# POWER.net
KiCad netlist of a schematic drawn in Altium Designer
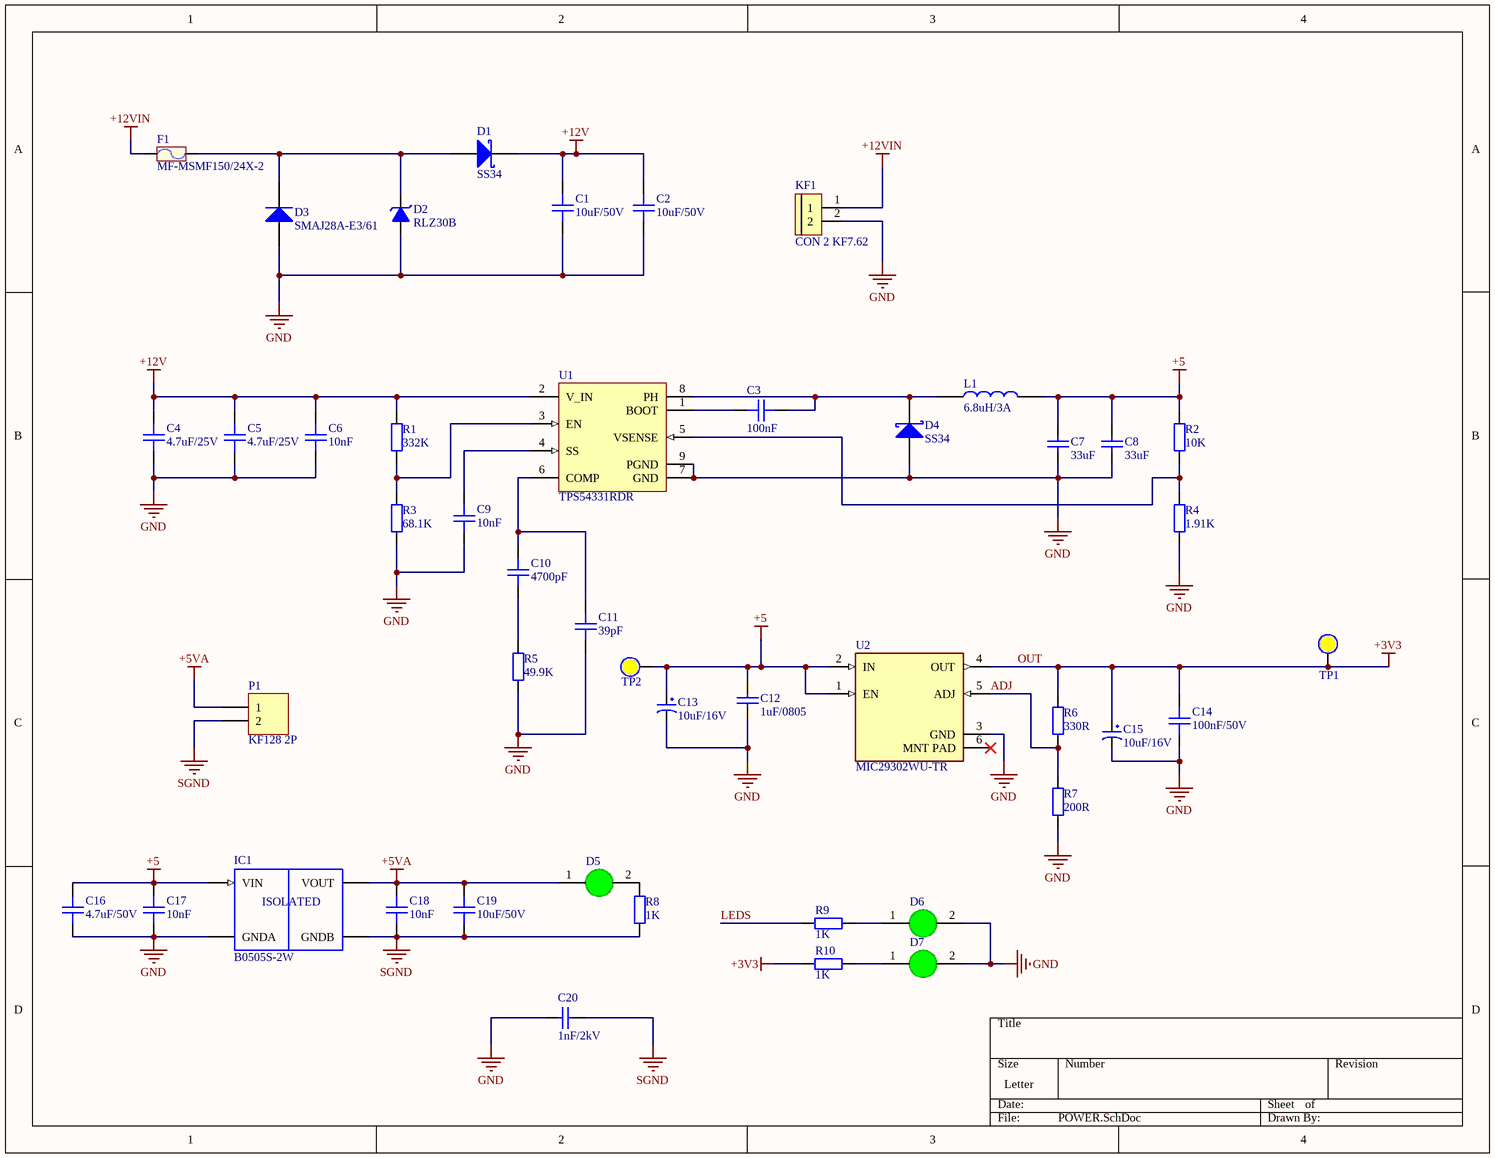
[diagram p0: POWER.SchDoc]

(export (version "E")
  (design (tool "Eeschema 10.0.6"))
  (components
    (comp (ref "C1")
      (value "10uF/50V")
      (footprint "1210")
      (description "CAP CER 10uF/50V 1210")
      (fields (field (name "MANUFACTURER") "Yageo") (field (name "PART NUMBER") "C1210"))
      (libsource (lib "Integrated_Library_gateway_tbl") (part "CAP_CER_1210_10uF"))
    )
    (comp (ref "C2")
      (value "10uF/50V")
      (footprint "1210")
      (description "CAP CER 10uF/50V 1210")
      (fields (field (name "MANUFACTURER") "Yageo") (field (name "PART NUMBER") "C1210"))
      (libsource (lib "Integrated_Library_gateway_tbl") (part "CAP_CER_1210_10uF"))
    )
    (comp (ref "C3")
      (value "100nF")
      (footprint "CAPC-0603 (1608)")
      (description "CAP CER 0.22UF 50V Y5V 0603")
      (fields (field (name "MPN") "CC0603ZRY5V9BB224"))
      (libsource (lib "Integrated_Library_gateway_tbl") (part "CC0603ZRY5V9BB224"))
    )
    (comp (ref "C4")
      (value "4.7uF/25V")
      (footprint "CAPC-1210 (3225)")
      (description "CAP CER 1UF 50V X7R 1210")
      (fields (field (name "MPN") "CC1210KKX7R9BB105") (field (name "MFR") "Yageo"))
      (libsource (lib "Integrated_Library_gateway_tbl") (part "CC1210KKX7R9BB105"))
    )
    (comp (ref "C5")
      (value "4.7uF/25V")
      (footprint "CAPC-1210 (3225)")
      (description "CAP CER 1UF 50V X7R 1210")
      (fields (field (name "MPN") "CC1210KKX7R9BB105") (field (name "MFR") "Yageo"))
      (libsource (lib "Integrated_Library_gateway_tbl") (part "CC1210KKX7R9BB105"))
    )
    (comp (ref "C6")
      (value "10nF")
      (footprint "CAPC-0603 (1608)")
      (description "CAP CER 10nF 16V 10% X7R 0603")
      (fields (field (name "MPN") "CC0603KRX7R7BB103"))
      (libsource (lib "Integrated_Library_gateway_tbl") (part "CC0603KRX7R7BB103"))
    )
    (comp (ref "C7")
      (value "33uF")
      (footprint "tu 1206")
      (description "Dán")
      (libsource (lib "Integrated_Library_gateway_tbl") (part "Tu 1206 100pF 50V 5%"))
    )
    (comp (ref "C8")
      (value "33uF")
      (footprint "tu 1206")
      (description "Dán")
      (libsource (lib "Integrated_Library_gateway_tbl") (part "Tu 1206 100pF 50V 5%"))
    )
    (comp (ref "C9")
      (value "10nF")
      (footprint "CAPC-0603 (1608)")
      (description "CAP CER 10nF 16V 10% X7R 0603")
      (fields (field (name "MPN") "CC0603KRX7R7BB103"))
      (libsource (lib "Integrated_Library_gateway_tbl") (part "CC0603KRX7R7BB103"))
    )
    (comp (ref "C10")
      (value "4700pF")
      (footprint "CAPC-0603 (1608)")
      (description "CAP CER 8200PF 50V X7R 0603")
      (fields (field (name "MPN") "CC0603KRX7R9BB822") (field (name "MFR") "Yageo"))
      (libsource (lib "Integrated_Library_gateway_tbl") (part "CC0603KRX7R9BB822"))
    )
    (comp (ref "C11")
      (value "39pF")
      (footprint "CAPC-0603 (1608)")
      (description "CAP CER 56PF 50V 5% COG/NPO 0603")
      (fields (field (name "MPN") "CC0603JRNPO9BN560"))
      (libsource (lib "Integrated_Library_gateway_tbl") (part "CC0603JRNPO9BN560"))
    )
    (comp (ref "C12")
      (value "1uF/0805")
      (footprint "tu 0805")
      (description "Dán")
      (libsource (lib "Integrated_Library_gateway_tbl") (part "Tu 0805 104 50V 10%"))
    )
    (comp (ref "C13")
      (value "10uF/16V")
      (footprint "2312")
      (description "CAP TANT 100uF/10V 2312")
      (fields (field (name "MANUFACTURER") "AVX") (field (name "PART NUMBER") "TAJC107K010RNJ"))
      (libsource (lib "Integrated_Library_gateway_tbl") (part "CAP_TANT_2312_100uF"))
    )
    (comp (ref "C14")
      (value "100nF/50V")
      (footprint "C0805")
      (description "CAP CER 100nF/50V 0805")
      (fields (field (name "MANUFACTURER") "Samsung") (field (name "PART NUMBER") "C0805"))
      (libsource (lib "Integrated_Library_gateway_tbl") (part "CAP_CER_0805_100nF"))
    )
    (comp (ref "C15")
      (value "10uF/16V")
      (footprint "2312")
      (description "CAP TANT 100uF/10V 2312")
      (fields (field (name "MANUFACTURER") "AVX") (field (name "PART NUMBER") "TAJC107K010RNJ"))
      (libsource (lib "Integrated_Library_gateway_tbl") (part "CAP_TANT_2312_100uF"))
    )
    (comp (ref "C16")
      (value "4.7uF/50V")
      (footprint "CAPC-0805 (2012)")
      (description "CAP CER 4.7uF -20% +80% 10V Y5V 0805")
      (fields (field (name "MPN") "CC0805ZRY5V6BB475"))
      (libsource (lib "Integrated_Library_gateway_tbl") (part "CC0805ZRY5V6BB475"))
    )
    (comp (ref "C17")
      (value "10nF")
      (footprint "CAPC-0603 (1608)")
      (description "CAP CER 10nF 16V 10% X7R 0603")
      (fields (field (name "MPN") "CC0603KRX7R7BB103"))
      (libsource (lib "Integrated_Library_gateway_tbl") (part "CC0603KRX7R7BB103"))
    )
    (comp (ref "C18")
      (value "10nF")
      (footprint "CAPC-0603 (1608)")
      (description "CAP CER 10nF 16V 10% X7R 0603")
      (fields (field (name "MPN") "CC0603KRX7R7BB103"))
      (libsource (lib "Integrated_Library_gateway_tbl") (part "CC0603KRX7R7BB103"))
    )
    (comp (ref "C19")
      (value "10uF/50V")
      (footprint "CAPC-0805 (2012)")
      (description "CAP CER 22uF 20% 10V X5R 0805")
      (fields (field (name "MPN") "CC0805MKX5R6BB226"))
      (libsource (lib "Integrated_Library_gateway_tbl") (part "CC0805MKX5R6BB226"))
    )
    (comp (ref "C20")
      (value "1nF/2kV")
      (footprint "tu 1206")
      (description "Dán")
      (libsource (lib "Integrated_Library_gateway_tbl") (part "Tu 1206 470pF 50V 10%"))
    )
    (comp (ref "D1")
      (value "SS34")
      (footprint "DIODE_DO214AC_SMA")
      (description "DIODE SCHOTTKY 40V 3A SMA")
      (libsource (lib "Integrated_Library_gateway_tbl") (part "SS34"))
    )
    (comp (ref "D2")
      (value "RLZ30B")
      (footprint "SOD_80")
      (description "ZMM15 15V 500mW SMD SOD-80")
      (fields (field (name "MANUFACTURER") "On Semiconductor") (field (name "PART NUMBER") "ZMM15"))
      (libsource (lib "Integrated_Library_gateway_tbl") (part "DIO_ZMM15"))
    )
    (comp (ref "D3")
      (value "SMAJ28A-E3/61")
      (footprint "VISH-DO-214AC-2_L")
      (fields (field (name "MANUFACTURER") "Vishay Semiconductor"))
      (libsource (lib "Integrated_Library_gateway_tbl") (part "VISH-K1A2-2"))
    )
    (comp (ref "D4")
      (value "SS34")
      (footprint "DIODE_DO214AC_SMA")
      (description "DIODE SCHOTTKY 40V 3A SMA")
      (libsource (lib "Integrated_Library_gateway_tbl") (part "SS34"))
    )
    (comp (ref "D5")
      (value "~")
      (footprint "LED_0805_GREEN")
      (description "LED GREEN CLEAR 2V4 20mA 0805 SMD")
      (fields (field (name "MPN") "17-21/G6C-FM1N2B/3T"))
      (libsource (lib "Integrated_Library_gateway_tbl") (part "17-21/G6C-FM1N2B/3T"))
    )
    (comp (ref "D6")
      (value "~")
      (footprint "LED_0805_GREEN")
      (description "LED GREEN CLEAR 2V4 20mA 0805 SMD")
      (fields (field (name "MPN") "17-21/G6C-FM1N2B/3T"))
      (libsource (lib "Integrated_Library_gateway_tbl") (part "17-21/G6C-FM1N2B/3T"))
    )
    (comp (ref "D7")
      (value "~")
      (footprint "LED_0805_GREEN")
      (description "LED GREEN CLEAR 2V4 20mA 0805 SMD")
      (fields (field (name "MPN") "17-21/G6C-FM1N2B/3T"))
      (libsource (lib "Integrated_Library_gateway_tbl") (part "17-21/G6C-FM1N2B/3T"))
    )
    (comp (ref "F1")
      (value "MF-MSMF150/24X-2")
      (footprint "1812")
      (description "MF-MSMF250/16 16V 2.5A1812")
      (fields (field (name "MANUFACTURER") "Bourns") (field (name "PART NUMBER") "1812"))
      (libsource (lib "Integrated_Library_gateway_tbl") (part "FUSE_16V_2.5A"))
    )
    (comp (ref "IC1")
      (value "B0505S-2W")
      (footprint "B0505S-2W")
      (fields (field (name "MF") "MORNSUN"))
      (libsource (lib "Integrated_Library_gateway_tbl") (part "B0505S-2W"))
    )
    (comp (ref "KF1")
      (value "CON 2 KF7.62")
      (footprint "CON 2 KF7.62")
      (description "Cắm")
      (libsource (lib "Altium_Lib_by_KhueNguyenCreator") (part "CON 2 KF7.62"))
    )
    (comp (ref "L1")
      (value "6.8uH/3A")
      (footprint "Cuon Cam 12x12x10")
      (description "Dán")
      (libsource (lib "Integrated_Library_gateway_tbl") (part "CUON CAM 100uH SMD"))
    )
    (comp (ref "P1")
      (value "KF128 2P")
      (footprint "KF128_2P")
      (description "Header, 2-Pin, pitch 5.08mm")
      (fields (field (name "MPN") "KF128-2P"))
      (libsource (lib "Integrated_Library_gateway_tbl") (part "KF128 2P"))
    )
    (comp (ref "R1")
      (value "332K")
      (footprint "RESC-0603 (1608)")
      (description "RES SMD 330K OHM 1% 1/10W 0603")
      (fields (field (name "MPN") "RC0603FR-07330KL"))
      (libsource (lib "Integrated_Library_gateway_tbl") (part "RC0603FR-07330KL"))
    )
    (comp (ref "R2")
      (value "10K")
      (footprint "RESC-0805 (2012)")
      (description "RES SMD 10K OHM 1% 1/8W 0805")
      (fields (field (name "MPN") "RC0805FR-0710KL"))
      (libsource (lib "Integrated_Library_gateway_tbl") (part "RC0805FR-0710KL"))
    )
    (comp (ref "R3")
      (value "68.1K")
      (footprint "RESC-0603 (1608)")
      (description "RES SMD 68K OHM 1% 1/10W 0603")
      (fields (field (name "MPN") "RC0603FR-0768KL"))
      (libsource (lib "Integrated_Library_gateway_tbl") (part "RC0603FR-0768KL"))
    )
    (comp (ref "R4")
      (value "1.91K")
      (footprint "RESC-0805 (2012)")
      (description "RES SMD 1.1K OHM 1% 1/8W 0805")
      (fields (field (name "MPN") "RC0805FR-071K1L"))
      (libsource (lib "Integrated_Library_gateway_tbl") (part "RC0805FR-071K1L"))
    )
    (comp (ref "R5")
      (value "49.9K")
      (footprint "RESC-0603 (1608)")
      (description "RES SMD 47K OHM 1% 1/10W 0603")
      (fields (field (name "MPN") "RC0603FR0747KL"))
      (libsource (lib "Integrated_Library_gateway_tbl") (part "RC0603FR0747KL"))
    )
    (comp (ref "R6")
      (value "330R")
      (footprint "RESC-0805 (2012)")
      (description "RES SMD 330 OHM 1% 1/8W 0805")
      (fields (field (name "MPN") "RC0805FR-07330RL"))
      (libsource (lib "Integrated_Library_gateway_tbl") (part "RC0805FR-07330RL"))
    )
    (comp (ref "R7")
      (value "200R")
      (footprint "RESC-0805 (2012)")
      (description "RES SMD 300 OHM 1% 1/8W 0805")
      (fields (field (name "MPN") "RC0805FR-07300RL"))
      (libsource (lib "Integrated_Library_gateway_tbl") (part "RC0805FR-07300RL"))
    )
    (comp (ref "R8")
      (value "1K")
      (footprint "RESC-0805 (2012)")
      (description "RES SMD 1K OHM 1% 1/8W 0805")
      (fields (field (name "MPN") "RC0805FR-071KL"))
      (libsource (lib "Integrated_Library_gateway_tbl") (part "RC0805FR-071KL"))
    )
    (comp (ref "R9")
      (value "1K")
      (footprint "RESC-0805 (2012)")
      (description "RES SMD 1K OHM 1% 1/8W 0805")
      (fields (field (name "MPN") "RC0805FR-071KL"))
      (libsource (lib "") (part "RC0805FR-071KL_1"))
    )
    (comp (ref "R10")
      (value "1K")
      (footprint "RESC-0805 (2012)")
      (description "RES SMD 1K OHM 1% 1/8W 0805")
      (fields (field (name "MPN") "RC0805FR-071KL"))
      (libsource (lib "") (part "RC0805FR-071KL_1"))
    )
    (comp (ref "TP1")
      (value "~")
      (footprint "Test Point 1 MM")
      (description "Test Point")
      (libsource (lib "Integrated_Library_gateway_tbl") (part "Test Point"))
    )
    (comp (ref "TP2")
      (value "~")
      (footprint "Test Point 1 MM")
      (description "Test Point")
      (libsource (lib "") (part "Test Point_1"))
    )
    (comp (ref "U1")
      (value "TPS54331RDR")
      (footprint "SOIC-8-TP")
      (description "Step Down DC-DC Converter")
      (fields (field (name "MPN") "TPS54360DDAR"))
      (libsource (lib "Integrated_Library_gateway_tbl") (part "TPS54360DDAR"))
    )
    (comp (ref "U2")
      (value "MIC29302WU-TR")
      (footprint "FP-C04-012-MFG")
      (description "IC REG LINEAR POS ADJ 3A TO263-5")
      (fields
        (field (name "MANUFACTURER") "Microchip")
        (field (name "OCTOPART") "https://octopart.com/mic29302wu-tr-microchip-66801318")
      )
      (libsource (lib "Integrated_Library_gateway_tbl") (part "0db40f55fda0e91d0d14528974a446d"))
    )
  )
  (nets
    (net (code "1") (name "+3V3") (class "Default")
      (node (ref "C14") (pin "2") (pinfunction "2_2") (pintype "passive"))
      (node (ref "C15") (pin "1") (pinfunction "1_1") (pintype "passive"))
      (node (ref "R10") (pin "1") (pinfunction "1_1") (pintype "passive"))
      (node (ref "R6") (pin "2") (pinfunction "2_2") (pintype "passive"))
      (node (ref "TP1") (pin "0") (pinfunction "0_0") (pintype "passive"))
      (node (ref "U2") (pin "4") (pinfunction "OUT_4") (pintype "output"))
    )
    (net (code "2") (name "+5") (class "Default")
      (node (ref "C12") (pin "1") (pinfunction "1_1") (pintype "passive"))
      (node (ref "C13") (pin "1") (pinfunction "1_1") (pintype "passive"))
      (node (ref "C16") (pin "2") (pinfunction "2_2") (pintype "passive"))
      (node (ref "C17") (pin "2") (pinfunction "2_2") (pintype "passive"))
      (node (ref "C7") (pin "1") (pinfunction "1_1") (pintype "passive"))
      (node (ref "C8") (pin "1") (pinfunction "1_1") (pintype "passive"))
      (node (ref "IC1") (pin "VIN") (pinfunction "VIN_VIN") (pintype "input"))
      (node (ref "L1") (pin "2") (pinfunction "2_2") (pintype "passive"))
      (node (ref "R2") (pin "2") (pinfunction "2_2") (pintype "passive"))
      (node (ref "TP2") (pin "0") (pinfunction "0_0") (pintype "passive"))
      (node (ref "U2") (pin "1") (pinfunction "EN_1") (pintype "input"))
      (node (ref "U2") (pin "2") (pinfunction "IN_2") (pintype "input"))
    )
    (net (code "3") (name "+5VA") (class "Default")
      (node (ref "C18") (pin "2") (pinfunction "2_2") (pintype "passive"))
      (node (ref "C19") (pin "2") (pinfunction "2_2") (pintype "passive"))
      (node (ref "D5") (pin "1") (pinfunction "A_1") (pintype "passive"))
      (node (ref "IC1") (pin "VOUT") (pinfunction "VOUT_VOUT") (pintype "power_in"))
      (node (ref "P1") (pin "1") (pinfunction "1_1") (pintype "passive"))
    )
    (net (code "4") (name "+12V") (class "Default")
      (node (ref "C1") (pin "2") (pinfunction "2_2") (pintype "passive"))
      (node (ref "C2") (pin "2") (pinfunction "2_2") (pintype "passive"))
      (node (ref "C4") (pin "2") (pinfunction "2_2") (pintype "passive"))
      (node (ref "C5") (pin "2") (pinfunction "2_2") (pintype "passive"))
      (node (ref "C6") (pin "2") (pinfunction "2_2") (pintype "passive"))
      (node (ref "D1") (pin "2") (pinfunction "K_2") (pintype "passive"))
      (node (ref "R1") (pin "2") (pinfunction "2_2") (pintype "passive"))
      (node (ref "U1") (pin "2") (pinfunction "V_IN_2") (pintype "passive"))
    )
    (net (code "5") (name "+12VIN") (class "Default")
      (node (ref "F1") (pin "1") (pinfunction "1_1") (pintype "passive"))
      (node (ref "KF1") (pin "1") (pinfunction "1_1") (pintype "passive"))
    )
    (net (code "6") (name "/ADJ") (class "Default")
      (node (ref "R6") (pin "1") (pinfunction "1_1") (pintype "passive"))
      (node (ref "R7") (pin "2") (pinfunction "2_2") (pintype "passive"))
      (node (ref "U2") (pin "5") (pinfunction "ADJ_5") (pintype "input"))
    )
    (net (code "7") (name "/LEDS") (class "Default")
      (node (ref "R9") (pin "1") (pinfunction "1_1") (pintype "passive"))
    )
    (net (code "8") (name "GND") (class "Default")
      (node (ref "C1") (pin "1") (pinfunction "1_1") (pintype "passive"))
      (node (ref "C11") (pin "1") (pinfunction "1_1") (pintype "passive"))
      (node (ref "C12") (pin "2") (pinfunction "2_2") (pintype "passive"))
      (node (ref "C13") (pin "2") (pinfunction "2_2") (pintype "passive"))
      (node (ref "C14") (pin "1") (pinfunction "1_1") (pintype "passive"))
      (node (ref "C15") (pin "2") (pinfunction "2_2") (pintype "passive"))
      (node (ref "C16") (pin "1") (pinfunction "1_1") (pintype "passive"))
      (node (ref "C17") (pin "1") (pinfunction "1_1") (pintype "passive"))
      (node (ref "C2") (pin "1") (pinfunction "1_1") (pintype "passive"))
      (node (ref "C20") (pin "2") (pinfunction "2_2") (pintype "passive"))
      (node (ref "C4") (pin "1") (pinfunction "1_1") (pintype "passive"))
      (node (ref "C5") (pin "1") (pinfunction "1_1") (pintype "passive"))
      (node (ref "C6") (pin "1") (pinfunction "1_1") (pintype "passive"))
      (node (ref "C7") (pin "2") (pinfunction "2_2") (pintype "passive"))
      (node (ref "C8") (pin "2") (pinfunction "2_2") (pintype "passive"))
      (node (ref "C9") (pin "1") (pinfunction "1_1") (pintype "passive"))
      (node (ref "D2") (pin "1") (pinfunction "A_1") (pintype "passive"))
      (node (ref "D3") (pin "2") (pinfunction "A_2") (pintype "passive"))
      (node (ref "D4") (pin "1") (pinfunction "A_1") (pintype "passive"))
      (node (ref "D6") (pin "2") (pinfunction "K_2") (pintype "passive"))
      (node (ref "D7") (pin "2") (pinfunction "K_2") (pintype "passive"))
      (node (ref "IC1") (pin "GNDA") (pinfunction "GNDA_GNDA") (pintype "power_in"))
      (node (ref "KF1") (pin "2") (pinfunction "2_2") (pintype "passive"))
      (node (ref "R3") (pin "1") (pinfunction "1_1") (pintype "passive"))
      (node (ref "R4") (pin "1") (pinfunction "1_1") (pintype "passive"))
      (node (ref "R5") (pin "1") (pinfunction "1_1") (pintype "passive"))
      (node (ref "R7") (pin "1") (pinfunction "1_1") (pintype "passive"))
      (node (ref "U1") (pin "7") (pinfunction "GND_7") (pintype "passive"))
      (node (ref "U1") (pin "9") (pinfunction "PGND_9") (pintype "passive"))
      (node (ref "U2") (pin "3") (pinfunction "GND_3") (pintype "power_in"))
    )
    (net (code "9") (name "Net-(C10-Pad1)") (class "Default")
      (node (ref "C10") (pin "1") (pinfunction "1_1") (pintype "passive"))
      (node (ref "R5") (pin "2") (pinfunction "2_2") (pintype "passive"))
    )
    (net (code "10") (name "Net-(D1-A)") (class "Default")
      (node (ref "D1") (pin "1") (pinfunction "A_1") (pintype "passive"))
      (node (ref "D2") (pin "2") (pinfunction "K_2") (pintype "passive"))
      (node (ref "D3") (pin "1") (pinfunction "K_1") (pintype "passive"))
      (node (ref "F1") (pin "2") (pinfunction "2_2") (pintype "passive"))
    )
    (net (code "11") (name "Net-(D4-K)") (class "Default")
      (node (ref "C3") (pin "2") (pinfunction "2_2") (pintype "passive"))
      (node (ref "D4") (pin "2") (pinfunction "K_2") (pintype "passive"))
      (node (ref "L1") (pin "1") (pinfunction "1_1") (pintype "passive"))
      (node (ref "U1") (pin "8") (pinfunction "PH_8") (pintype "passive"))
    )
    (net (code "12") (name "Net-(D5-K)") (class "Default")
      (node (ref "D5") (pin "2") (pinfunction "K_2") (pintype "passive"))
      (node (ref "R8") (pin "1") (pinfunction "1_1") (pintype "passive"))
    )
    (net (code "13") (name "Net-(D6-A)") (class "Default")
      (node (ref "D6") (pin "1") (pinfunction "A_1") (pintype "passive"))
      (node (ref "R9") (pin "2") (pinfunction "2_2") (pintype "passive"))
    )
    (net (code "14") (name "Net-(D7-A)") (class "Default")
      (node (ref "D7") (pin "1") (pinfunction "A_1") (pintype "passive"))
      (node (ref "R10") (pin "2") (pinfunction "2_2") (pintype "passive"))
    )
    (net (code "15") (name "Net-(U1-BOOT)") (class "Default")
      (node (ref "C3") (pin "1") (pinfunction "1_1") (pintype "passive"))
      (node (ref "U1") (pin "1") (pinfunction "BOOT_1") (pintype "passive"))
    )
    (net (code "16") (name "Net-(U1-COMP)") (class "Default")
      (node (ref "C10") (pin "2") (pinfunction "2_2") (pintype "passive"))
      (node (ref "C11") (pin "2") (pinfunction "2_2") (pintype "passive"))
      (node (ref "U1") (pin "6") (pinfunction "COMP_6") (pintype "passive"))
    )
    (net (code "17") (name "Net-(U1-EN)") (class "Default")
      (node (ref "R1") (pin "1") (pinfunction "1_1") (pintype "passive"))
      (node (ref "R3") (pin "2") (pinfunction "2_2") (pintype "passive"))
      (node (ref "U1") (pin "3") (pinfunction "EN_3") (pintype "input"))
    )
    (net (code "18") (name "Net-(U1-SS)") (class "Default")
      (node (ref "C9") (pin "2") (pinfunction "2_2") (pintype "passive"))
      (node (ref "U1") (pin "4") (pinfunction "SS_4") (pintype "input"))
    )
    (net (code "19") (name "Net-(U1-VSENSE)") (class "Default")
      (node (ref "R2") (pin "1") (pinfunction "1_1") (pintype "passive"))
      (node (ref "R4") (pin "2") (pinfunction "2_2") (pintype "passive"))
      (node (ref "U1") (pin "5") (pinfunction "VSENSE_5") (pintype "input"))
    )
    (net (code "20") (name "SGND") (class "Default")
      (node (ref "C18") (pin "1") (pinfunction "1_1") (pintype "passive"))
      (node (ref "C19") (pin "1") (pinfunction "1_1") (pintype "passive"))
      (node (ref "C20") (pin "1") (pinfunction "1_1") (pintype "passive"))
      (node (ref "IC1") (pin "GNDB") (pinfunction "GNDB_GNDB") (pintype "power_in"))
      (node (ref "P1") (pin "2") (pinfunction "2_2") (pintype "passive"))
      (node (ref "R8") (pin "2") (pinfunction "2_2") (pintype "passive"))
    )
    (net (code "21") (name "unconnected-(U2-MNT_PAD-Pad6)") (class "Default")
      (node (ref "U2") (pin "6") (pinfunction "MNT_PAD_6") (pintype "passive+no_connect"))
    )
  )
)
